# BACKPMAN21_CPU.net
KiCad netlist of a schematic drawn in Altium Designer
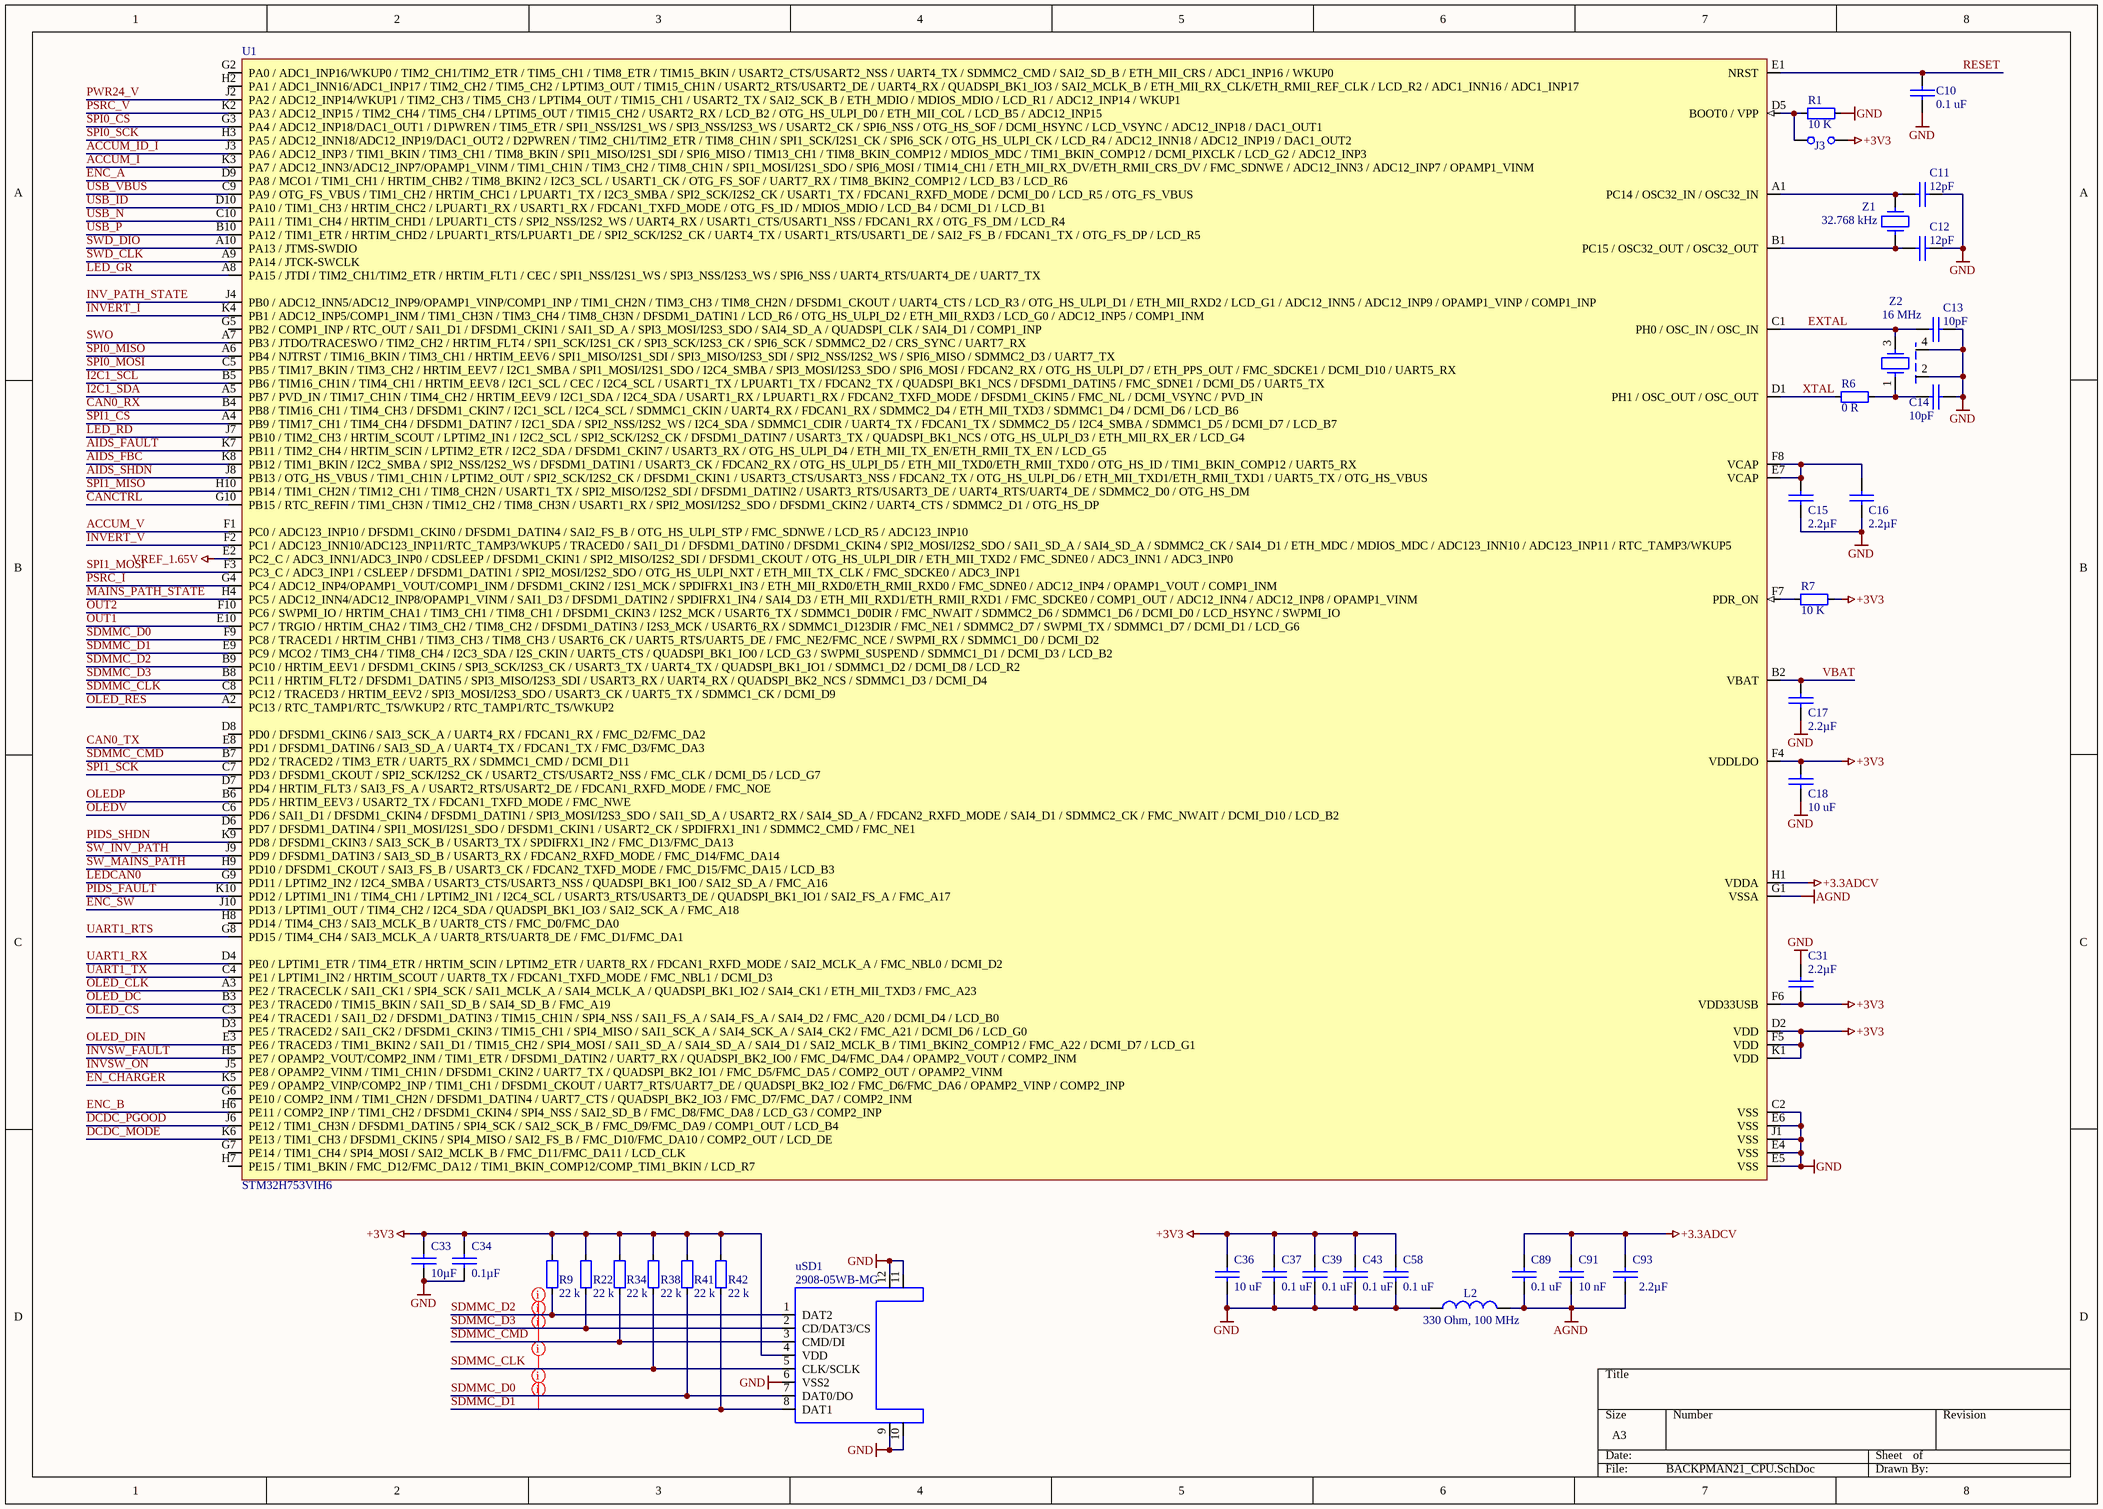
[diagram p0: BACKPMAN21_CPU.SchDoc]

(export (version "E")
  (design (tool "Eeschema 10.0.6"))
  (components
    (comp (ref "C10")
      (value "0.1 uF")
      (footprint "1608[0603]")
      (description "0.1 uF, 50V, 10% , X7R,  0603 SMD MLC Capacitor")
      (fields (field (name "TOLERANCE") "±10%") (field (name "MANUFACTURER") "WALSIN"))
      (libsource (lib "ea_Capacitors") (part "CVNF100K0603-25"))
    )
    (comp (ref "C11")
      (value "12pF")
      (footprint "0402 CAP")
      (description "12pF, ±2%, 50V, C0G, NP0, 0402 (1005 Metric), -55°C ~ 125°C, -, General Purpose")
      (fields
        (field (name "PART NUMBER") "0402N120G500CT")
        (field (name "MANUFACTURER") "Walsin Technology Corporation")
      )
      (libsource (lib "ea_PassivComps") (part "Capacitor"))
    )
    (comp (ref "C12")
      (value "12pF")
      (footprint "0402 CAP")
      (description "12pF, ±2%, 50V, C0G, NP0, 0402 (1005 Metric), -55°C ~ 125°C, -, General Purpose")
      (fields
        (field (name "PART NUMBER") "0402N120G500CT")
        (field (name "MANUFACTURER") "Walsin Technology Corporation")
      )
      (libsource (lib "ea_PassivComps") (part "Capacitor"))
    )
    (comp (ref "C13")
      (value "10pF")
      (footprint "0402 CAP")
      (description "10pF, ±1%, 50V, C0G, NP0, 0402 (1005 Metric), -55°C ~ 125°C, -, Automotive")
      (fields
        (field (name "PART NUMBER") "GCM1555C1H100FA16D")
        (field (name "MANUFACTURER") "Murata Electronics North America")
      )
      (libsource (lib "ea_PassivComps") (part "Capacitor"))
    )
    (comp (ref "C14")
      (value "10pF")
      (footprint "0402 CAP")
      (description "10pF, ±1%, 50V, C0G, NP0, 0402 (1005 Metric), -55°C ~ 125°C, -, Automotive")
      (fields
        (field (name "PART NUMBER") "GCM1555C1H100FA16D")
        (field (name "MANUFACTURER") "Murata Electronics North America")
      )
      (libsource (lib "ea_PassivComps") (part "Capacitor"))
    )
    (comp (ref "C15")
      (value "2.2µF")
      (footprint "0603 CAP")
      (description "2.2µF, ±10%, 16V, X5R, 0603 (1608 Metric), -55°C ~ 85°C, -, General Purpose")
      (fields (field (name "PART NUMBER") "CC0603KRX5R7BB225") (field (name "MANUFACTURER") "Yageo"))
      (libsource (lib "ea_PassivComps") (part "Capacitor"))
    )
    (comp (ref "C16")
      (value "2.2µF")
      (footprint "0603 CAP")
      (description "2.2µF, ±10%, 16V, X5R, 0603 (1608 Metric), -55°C ~ 85°C, -, General Purpose")
      (fields (field (name "PART NUMBER") "CC0603KRX5R7BB225") (field (name "MANUFACTURER") "Yageo"))
      (libsource (lib "ea_PassivComps") (part "Capacitor"))
    )
    (comp (ref "C17")
      (value "2.2µF")
      (footprint "0603 CAP")
      (description "2.2µF, ±10%, 16V, X5R, 0603 (1608 Metric), -55°C ~ 85°C, -, General Purpose")
      (fields (field (name "PART NUMBER") "CC0603KRX5R7BB225") (field (name "MANUFACTURER") "Yageo"))
      (libsource (lib "ea_PassivComps") (part "Capacitor"))
    )
    (comp (ref "C18")
      (value "10 uF")
      (footprint "0805-1206")
      (description "CAP CER 10UF 10V 10% X5R 0805")
      (fields (field (name "MANUFACTURER") "Taiyo Yuden") (field (name "TOLERANCE") "10%"))
      (libsource (lib "ea_Capacitors") (part "LMK212F106ZG-T"))
    )
    (comp (ref "C31")
      (value "2.2µF")
      (footprint "0603 CAP")
      (description "2.2µF, ±10%, 16V, X5R, 0603 (1608 Metric), -55°C ~ 85°C, -, General Purpose")
      (fields (field (name "PART NUMBER") "CC0603KRX5R7BB225") (field (name "MANUFACTURER") "Yageo"))
      (libsource (lib "ea_PassivComps") (part "Capacitor"))
    )
    (comp (ref "C33")
      (value "10µF")
      (footprint "0603 CAP")
      (description "10µF, ±10%, 16V, X5R, 0603 (1608 Metric), -55°C ~ 85°C, -, Automotive")
      (fields
        (field (name "PART NUMBER") "GRT188R61C106KE13D")
        (field (name "MANUFACTURER") "Murata Electronics North America")
      )
      (libsource (lib "ea_PassivComps") (part "Capacitor"))
    )
    (comp (ref "C34")
      (value "0.1µF")
      (footprint "0402 CAP")
      (description "0.1µF, ±10%, 50V, X7R, 0402 (1005 Metric), -55°C ~ 125°C, -, General Purpose")
      (fields
        (field (name "PART NUMBER") "0402B104K500CT")
        (field (name "MANUFACTURER") "Walsin Technology Corporation")
      )
      (libsource (lib "ea_PassivComps") (part "Capacitor"))
    )
    (comp (ref "C36")
      (value "10 uF")
      (footprint "0805-1206")
      (description "CAP CER 10UF 10V 10% X5R 0805")
      (fields (field (name "MANUFACTURER") "Taiyo Yuden") (field (name "TOLERANCE") "10%"))
      (libsource (lib "ea_Capacitors") (part "LMK212F106ZG-T"))
    )
    (comp (ref "C37")
      (value "0.1 uF")
      (footprint "1608[0603]")
      (description "0.1 uF, 50V, 10% , X7R,  0603 SMD MLC Capacitor")
      (fields (field (name "TOLERANCE") "±10%") (field (name "MANUFACTURER") "WALSIN"))
      (libsource (lib "ea_Capacitors") (part "CVNF100K0603-25"))
    )
    (comp (ref "C39")
      (value "0.1 uF")
      (footprint "1608[0603]")
      (description "0.1 uF, 50V, 10% , X7R,  0603 SMD MLC Capacitor")
      (fields (field (name "TOLERANCE") "±10%") (field (name "MANUFACTURER") "WALSIN"))
      (libsource (lib "ea_Capacitors") (part "CVNF100K0603-25"))
    )
    (comp (ref "C43")
      (value "0.1 uF")
      (footprint "1608[0603]")
      (description "0.1 uF, 50V, 10% , X7R,  0603 SMD MLC Capacitor")
      (fields (field (name "TOLERANCE") "±10%") (field (name "MANUFACTURER") "WALSIN"))
      (libsource (lib "ea_Capacitors") (part "CVNF100K0603-25"))
    )
    (comp (ref "C58")
      (value "0.1 uF")
      (footprint "1608[0603]")
      (description "0.1 uF, 50V, 10% , X7R,  0603 SMD MLC Capacitor")
      (fields (field (name "TOLERANCE") "±10%") (field (name "MANUFACTURER") "WALSIN"))
      (libsource (lib "ea_Capacitors") (part "CVNF100K0603-25"))
    )
    (comp (ref "C89")
      (value "0.1 uF")
      (footprint "1608[0603]")
      (description "0.1 uF, 50V, 10% , X7R,  0603 SMD MLC Capacitor")
      (fields (field (name "TOLERANCE") "±10%") (field (name "MANUFACTURER") "WALSIN"))
      (libsource (lib "ea_Capacitors") (part "CVNF100K0603-25"))
    )
    (comp (ref "C91")
      (value "10 nF")
      (footprint "1608[0603]")
      (description "10 nF, 50V, 10%, X7R, 0603 SMD MLC Capacitor")
      (fields (field (name "TOLERANCE") "±10%") (field (name "MANUFACTURER") "Murata Electronics"))
      (libsource (lib "ea_Capacitors") (part "CVNF010K0603"))
    )
    (comp (ref "C93")
      (value "2.2µF")
      (footprint "0603 CAP")
      (description "2.2µF, ±10%, 16V, X5R, 0603 (1608 Metric), -55°C ~ 85°C, -, General Purpose")
      (fields (field (name "PART NUMBER") "CC0603KRX5R7BB225") (field (name "MANUFACTURER") "Yageo"))
      (libsource (lib "ea_PassivComps") (part "Capacitor"))
    )
    (comp (ref "J3")
      (value "PH1-02-TA-HT")
      (footprint "HDR1X2V")
      (description "2 Pos. 2.54 mm Single Row Through Hole Straight Pin Header")
      (fields (field (name "MANUFACTURER") "ADAM TECH"))
      (libsource (lib "ea_Commutation") (part "Jumper"))
    )
    (comp (ref "L2")
      (value "330 Ohm, 100 MHz")
      (footprint "0603")
      (description "Ferrite bead, 330 Ohm, 100 MHz,  1.5 A, 0.07 Ohm")
      (fields
        (field (name "MANUFACTURER") "Murata Electronics North America")
        (field (name "PARTNUM") "BLM18SG331TN1D")
      )
      (libsource (lib "*") (part "BLM18SG331TN1D"))
    )
    (comp (ref "R1")
      (value "10 K")
      (footprint "0603")
      (description "10 K, 1%, 0603, SMD Resistor, Taped")
      (fields (field (name "MANUFACTURER") "Vishay") (field (name "TOLERANCE") "1%"))
      (libsource (lib "ea_Resistors_0603") (part "RL0603K010-1"))
    )
    (comp (ref "R6")
      (value "0 R")
      (footprint "0603")
      (description "0 R, Jumper, 0603, SMD Resistor, -55°C ~ 155°C")
      (fields (field (name "MANUFACTURER") "Yageo") (field (name "VOLTAGE") "75 V"))
      (libsource (lib "ea_Resistors_0603") (part "RC0603FR-070RL"))
    )
    (comp (ref "R7")
      (value "10 K")
      (footprint "0603")
      (description "10 K, 1%, 0603, SMD Resistor, Taped")
      (fields (field (name "MANUFACTURER") "Vishay") (field (name "TOLERANCE") "1%"))
      (libsource (lib "ea_Resistors_0603") (part "RL0603K010-1"))
    )
    (comp (ref "R9")
      (value "22 k")
      (footprint "0402")
      (fields
        (field (name "MANUFACTURER") "Stackpole Electronics Inc")
        (field (name "TOLERANCE") "±1%")
        (field (name "VOLTAGE") "75V")
      )
      (libsource (lib "ea_PassivComps") (part "Resistor"))
    )
    (comp (ref "R22")
      (value "22 k")
      (footprint "0402")
      (fields
        (field (name "MANUFACTURER") "Stackpole Electronics Inc")
        (field (name "TOLERANCE") "±1%")
        (field (name "VOLTAGE") "75V")
      )
      (libsource (lib "ea_PassivComps") (part "Resistor"))
    )
    (comp (ref "R34")
      (value "22 k")
      (footprint "0402")
      (fields
        (field (name "MANUFACTURER") "Stackpole Electronics Inc")
        (field (name "TOLERANCE") "±1%")
        (field (name "VOLTAGE") "75V")
      )
      (libsource (lib "ea_PassivComps") (part "Resistor"))
    )
    (comp (ref "R38")
      (value "22 k")
      (footprint "0402")
      (fields
        (field (name "MANUFACTURER") "Stackpole Electronics Inc")
        (field (name "TOLERANCE") "±1%")
        (field (name "VOLTAGE") "75V")
      )
      (libsource (lib "ea_PassivComps") (part "Resistor"))
    )
    (comp (ref "R41")
      (value "22 k")
      (footprint "0402")
      (fields
        (field (name "MANUFACTURER") "Stackpole Electronics Inc")
        (field (name "TOLERANCE") "±1%")
        (field (name "VOLTAGE") "75V")
      )
      (libsource (lib "ea_PassivComps") (part "Resistor"))
    )
    (comp (ref "R42")
      (value "22 k")
      (footprint "0402")
      (fields
        (field (name "MANUFACTURER") "Stackpole Electronics Inc")
        (field (name "TOLERANCE") "±1%")
        (field (name "VOLTAGE") "75V")
      )
      (libsource (lib "ea_PassivComps") (part "Resistor"))
    )
    (comp (ref "U1")
      (value "STM32H753VIH6")
      (footprint "TFBGA100")
      (description "Cortex-M7, 480MHz 2MB FLASH, 1MB RAM, 100-TFBGA (8x8)")
      (fields (field (name "MANUFACTURER") "STMicroelectronics") (field (name "PARTNUM") "STM32H753VIH6-ND"))
      (libsource (lib "ea_IC_CPU") (part "STM32H753VIH6"))
    )
    (comp (ref "uSD1")
      (value "2908-05WB-MG")
      (footprint "2908-05WB-MG")
      (description "microSD cadr holder")
      (fields (field (name "MANUFACTURER") "3M"))
      (libsource (lib "ea_CARD_holders") (part "2908-05WB-MG"))
    )
    (comp (ref "Z1")
      (value "32.768 kHz")
      (footprint "ABS7")
      (description "32.768 kHz, 12.5 pF, 70 kOhm, ±20ppm, 3.2 x 1.5 mm, -40°C ~ 85°C")
      (fields (field (name "MANUFACTURER") "Abracon Corporation") (field (name "PARTNUM") "535-9542-1-ND"))
      (libsource (lib "ea_OSC_CLK_GEN") (part "ABS07-32.768KHZ-T"))
    )
    (comp (ref "Z2")
      (value "16 MHz")
      (footprint "4-SMD 2.00mm x 1.60mm")
      (description "16 MHz, 9 pF, ±10ppm, 2.00mm x 1.60mm, -20°C ~ 70°C")
      (fields (field (name "MANUFACTURER") "Abracon LLC") (field (name "PARTNUM") "535-13598-1-ND"))
      (libsource (lib "ea_OSC_CLK_GEN") (part "ABM11-16.000MHZ-9-B1U-T"))
    )
  )
  (nets
    (net (code "1") (name "+3.3ADCV") (class "Default")
      (node (ref "C89") (pin "2") (pinfunction "2_2") (pintype "passive"))
      (node (ref "C91") (pin "1") (pinfunction "1_1") (pintype "passive"))
      (node (ref "C93") (pin "1") (pinfunction "1_1") (pintype "passive"))
      (node (ref "U1") (pin "H1") (pinfunction "VDDA_H1") (pintype "power_in"))
    )
    (net (code "2") (name "+3V3") (class "Default")
      (node (ref "C18") (pin "2") (pinfunction "2_2") (pintype "passive"))
      (node (ref "C31") (pin "2") (pinfunction "2_2") (pintype "passive"))
      (node (ref "C33") (pin "2") (pinfunction "2_2") (pintype "passive"))
      (node (ref "C34") (pin "2") (pinfunction "2_2") (pintype "passive"))
      (node (ref "C36") (pin "2") (pinfunction "2_2") (pintype "passive"))
      (node (ref "C37") (pin "2") (pinfunction "2_2") (pintype "passive"))
      (node (ref "C39") (pin "2") (pinfunction "2_2") (pintype "passive"))
      (node (ref "C43") (pin "2") (pinfunction "2_2") (pintype "passive"))
      (node (ref "C58") (pin "2") (pinfunction "2_2") (pintype "passive"))
      (node (ref "J3") (pin "2") (pinfunction "2_2") (pintype "passive"))
      (node (ref "R22") (pin "2") (pinfunction "2_2") (pintype "passive"))
      (node (ref "R34") (pin "2") (pinfunction "2_2") (pintype "passive"))
      (node (ref "R38") (pin "2") (pinfunction "2_2") (pintype "passive"))
      (node (ref "R41") (pin "2") (pinfunction "2_2") (pintype "passive"))
      (node (ref "R42") (pin "2") (pinfunction "2_2") (pintype "passive"))
      (node (ref "R7") (pin "1") (pinfunction "1_1") (pintype "passive"))
      (node (ref "R9") (pin "2") (pinfunction "2_2") (pintype "passive"))
      (node (ref "U1") (pin "D2") (pinfunction "VDD_D2") (pintype "power_in"))
      (node (ref "U1") (pin "F4") (pinfunction "VDDLDO_F4") (pintype "power_in"))
      (node (ref "U1") (pin "F5") (pinfunction "VDD_F5") (pintype "power_in"))
      (node (ref "U1") (pin "F6") (pinfunction "VDD33USB_F6") (pintype "power_in"))
      (node (ref "U1") (pin "K1") (pinfunction "VDD_K1") (pintype "power_in"))
      (node (ref "uSD1") (pin "4") (pinfunction "VDD_4") (pintype "passive"))
    )
    (net (code "3") (name "/ACCUM_I") (class "Default")
      (node (ref "U1") (pin "K3") (pinfunction "PA7_/_ADC12_INN3/ADC12_INP7/OPAMP1_VINM_/_TIM1_CH1N_/_TIM3_CH2_/_TIM8_CH1N_/_SPI1_MOSI/I2S1_SDO_/_SPI6_MOSI_/_TIM14_CH1_/_ETH_MII_RX_DV/ETH_RMII_CRS_DV_/_FMC_SDNWE_/_ADC12_INN3_/_ADC12_INP7_/_OPAMP1_VINM_K3") (pintype "bidirectional"))
    )
    (net (code "4") (name "/ACCUM_ID_I") (class "Default")
      (node (ref "U1") (pin "J3") (pinfunction "PA6_/_ADC12_INP3_/_TIM1_BKIN_/_TIM3_CH1_/_TIM8_BKIN_/_SPI1_MISO/I2S1_SDI_/_SPI6_MISO_/_TIM13_CH1_/_TIM8_BKIN_COMP12_/_MDIOS_MDC_/_TIM1_BKIN_COMP12_/_DCMI_PIXCLK_/_LCD_G2_/_ADC12_INP3_J3") (pintype "bidirectional"))
    )
    (net (code "5") (name "/ACCUM_V") (class "Default")
      (node (ref "U1") (pin "F1") (pinfunction "PC0_/_ADC123_INP10_/_DFSDM1_CKIN0_/_DFSDM1_DATIN4_/_SAI2_FS_B_/_OTG_HS_ULPI_STP_/_FMC_SDNWE_/_LCD_R5_/_ADC123_INP10_F1") (pintype "bidirectional"))
    )
    (net (code "6") (name "/AIDS_FAULT") (class "Default")
      (node (ref "U1") (pin "K7") (pinfunction "PB11_/_TIM2_CH4_/_HRTIM_SCIN_/_LPTIM2_ETR_/_I2C2_SDA_/_DFSDM1_CKIN7_/_USART3_RX_/_OTG_HS_ULPI_D4_/_ETH_MII_TX_EN/ETH_RMII_TX_EN_/_LCD_G5_K7") (pintype "bidirectional"))
    )
    (net (code "7") (name "/AIDS_FBC") (class "Default")
      (node (ref "U1") (pin "K8") (pinfunction "PB12_/_TIM1_BKIN_/_I2C2_SMBA_/_SPI2_NSS/I2S2_WS_/_DFSDM1_DATIN1_/_USART3_CK_/_FDCAN2_RX_/_OTG_HS_ULPI_D5_/_ETH_MII_TXD0/ETH_RMII_TXD0_/_OTG_HS_ID_/_TIM1_BKIN_COMP12_/_UART5_RX_K8") (pintype "bidirectional"))
    )
    (net (code "8") (name "/AIDS_SHDN") (class "Default")
      (node (ref "U1") (pin "J8") (pinfunction "PB13_/_OTG_HS_VBUS_/_TIM1_CH1N_/_LPTIM2_OUT_/_SPI2_SCK/I2S2_CK_/_DFSDM1_CKIN1_/_USART3_CTS/USART3_NSS_/_FDCAN2_TX_/_OTG_HS_ULPI_D6_/_ETH_MII_TXD1/ETH_RMII_TXD1_/_UART5_TX_/_OTG_HS_VBUS_J8") (pintype "bidirectional"))
    )
    (net (code "9") (name "/CAN0_RX") (class "Default")
      (node (ref "U1") (pin "B4") (pinfunction "PB8_/_TIM16_CH1_/_TIM4_CH3_/_DFSDM1_CKIN7_/_I2C1_SCL_/_I2C4_SCL_/_SDMMC1_CKIN_/_UART4_RX_/_FDCAN1_RX_/_SDMMC2_D4_/_ETH_MII_TXD3_/_SDMMC1_D4_/_DCMI_D6_/_LCD_B6_B4") (pintype "bidirectional"))
    )
    (net (code "10") (name "/CAN0_TX") (class "Default")
      (node (ref "U1") (pin "E8") (pinfunction "PD1_/_DFSDM1_DATIN6_/_SAI3_SD_A_/_UART4_TX_/_FDCAN1_TX_/_FMC_D3/FMC_DA3_E8") (pintype "bidirectional"))
    )
    (net (code "11") (name "/CANCTRL") (class "Default")
      (node (ref "U1") (pin "G10") (pinfunction "PB15_/_RTC_REFIN_/_TIM1_CH3N_/_TIM12_CH2_/_TIM8_CH3N_/_USART1_RX_/_SPI2_MOSI/I2S2_SDO_/_DFSDM1_CKIN2_/_UART4_CTS_/_SDMMC2_D1_/_OTG_HS_DP_G10") (pintype "bidirectional"))
    )
    (net (code "12") (name "/DCDC_MODE") (class "Default")
      (node (ref "U1") (pin "K6") (pinfunction "PE13_/_TIM1_CH3_/_DFSDM1_CKIN5_/_SPI4_MISO_/_SAI2_FS_B_/_FMC_D10/FMC_DA10_/_COMP2_OUT_/_LCD_DE_K6") (pintype "bidirectional"))
    )
    (net (code "13") (name "/DCDC_PGOOD") (class "Default")
      (node (ref "U1") (pin "J6") (pinfunction "PE12_/_TIM1_CH3N_/_DFSDM1_DATIN5_/_SPI4_SCK_/_SAI2_SCK_B_/_FMC_D9/FMC_DA9_/_COMP1_OUT_/_LCD_B4_J6") (pintype "bidirectional"))
    )
    (net (code "14") (name "/ENC_A") (class "Default")
      (node (ref "U1") (pin "D9") (pinfunction "PA8_/_MCO1_/_TIM1_CH1_/_HRTIM_CHB2_/_TIM8_BKIN2_/_I2C3_SCL_/_USART1_CK_/_OTG_FS_SOF_/_UART7_RX_/_TIM8_BKIN2_COMP12_/_LCD_B3_/_LCD_R6_D9") (pintype "bidirectional"))
    )
    (net (code "15") (name "/ENC_B") (class "Default")
      (node (ref "U1") (pin "H6") (pinfunction "PE11_/_COMP2_INP_/_TIM1_CH2_/_DFSDM1_CKIN4_/_SPI4_NSS_/_SAI2_SD_B_/_FMC_D8/FMC_DA8_/_LCD_G3_/_COMP2_INP_H6") (pintype "bidirectional"))
    )
    (net (code "16") (name "/ENC_SW") (class "Default")
      (node (ref "U1") (pin "J10") (pinfunction "PD13_/_LPTIM1_OUT_/_TIM4_CH2_/_I2C4_SDA_/_QUADSPI_BK1_IO3_/_SAI2_SCK_A_/_FMC_A18_J10") (pintype "bidirectional"))
    )
    (net (code "17") (name "/EN_CHARGER") (class "Default")
      (node (ref "U1") (pin "K5") (pinfunction "PE9_/_OPAMP2_VINP/COMP2_INP_/_TIM1_CH1_/_DFSDM1_CKOUT_/_UART7_RTS/UART7_DE_/_QUADSPI_BK2_IO2_/_FMC_D6/FMC_DA6_/_OPAMP2_VINP_/_COMP2_INP_K5") (pintype "bidirectional"))
    )
    (net (code "18") (name "/EXTAL") (class "Default")
      (node (ref "C13") (pin "1") (pinfunction "1_1") (pintype "passive"))
      (node (ref "U1") (pin "C1") (pinfunction "PH0_/_OSC_IN_/_OSC_IN_C1") (pintype "bidirectional"))
      (node (ref "Z2") (pin "3") (pinfunction "3_3") (pintype "passive"))
    )
    (net (code "19") (name "/I2C1_SCL") (class "Default")
      (node (ref "U1") (pin "B5") (pinfunction "PB6_/_TIM16_CH1N_/_TIM4_CH1_/_HRTIM_EEV8_/_I2C1_SCL_/_CEC_/_I2C4_SCL_/_USART1_TX_/_LPUART1_TX_/_FDCAN2_TX_/_QUADSPI_BK1_NCS_/_DFSDM1_DATIN5_/_FMC_SDNE1_/_DCMI_D5_/_UART5_TX_B5") (pintype "bidirectional"))
    )
    (net (code "20") (name "/I2C1_SDA") (class "Default")
      (node (ref "U1") (pin "A5") (pinfunction "PB7_/_PVD_IN_/_TIM17_CH1N_/_TIM4_CH2_/_HRTIM_EEV9_/_I2C1_SDA_/_I2C4_SDA_/_USART1_RX_/_LPUART1_RX_/_FDCAN2_TXFD_MODE_/_DFSDM1_CKIN5_/_FMC_NL_/_DCMI_VSYNC_/_PVD_IN_A5") (pintype "bidirectional"))
    )
    (net (code "21") (name "/INVERT_I") (class "Default")
      (node (ref "U1") (pin "K4") (pinfunction "PB1_/_ADC12_INP5/COMP1_INM_/_TIM1_CH3N_/_TIM3_CH4_/_TIM8_CH3N_/_DFSDM1_DATIN1_/_LCD_R6_/_OTG_HS_ULPI_D2_/_ETH_MII_RXD3_/_LCD_G0_/_ADC12_INP5_/_COMP1_INM_K4") (pintype "bidirectional"))
    )
    (net (code "22") (name "/INVERT_V") (class "Default")
      (node (ref "U1") (pin "F2") (pinfunction "PC1_/_ADC123_INN10/ADC123_INP11/RTC_TAMP3/WKUP5_/_TRACED0_/_SAI1_D1_/_DFSDM1_DATIN0_/_DFSDM1_CKIN4_/_SPI2_MOSI/I2S2_SDO_/_SAI1_SD_A_/_SAI4_SD_A_/_SDMMC2_CK_/_SAI4_D1_/_ETH_MDC_/_MDIOS_MDC_/_ADC123_INN10_/_ADC123_INP11_/_RTC_TAMP3/WKUP5_F2") (pintype "bidirectional"))
    )
    (net (code "23") (name "/INVSW_FAULT") (class "Default")
      (node (ref "U1") (pin "H5") (pinfunction "PE7_/_OPAMP2_VOUT/COMP2_INM_/_TIM1_ETR_/_DFSDM1_DATIN2_/_UART7_RX_/_QUADSPI_BK2_IO0_/_FMC_D4/FMC_DA4_/_OPAMP2_VOUT_/_COMP2_INM_H5") (pintype "bidirectional"))
    )
    (net (code "24") (name "/INVSW_ON") (class "Default")
      (node (ref "U1") (pin "J5") (pinfunction "PE8_/_OPAMP2_VINM_/_TIM1_CH1N_/_DFSDM1_CKIN2_/_UART7_TX_/_QUADSPI_BK2_IO1_/_FMC_D5/FMC_DA5_/_COMP2_OUT_/_OPAMP2_VINM_J5") (pintype "bidirectional"))
    )
    (net (code "25") (name "/INV_PATH_STATE") (class "Default")
      (node (ref "U1") (pin "J4") (pinfunction "PB0_/_ADC12_INN5/ADC12_INP9/OPAMP1_VINP/COMP1_INP_/_TIM1_CH2N_/_TIM3_CH3_/_TIM8_CH2N_/_DFSDM1_CKOUT_/_UART4_CTS_/_LCD_R3_/_OTG_HS_ULPI_D1_/_ETH_MII_RXD2_/_LCD_G1_/_ADC12_INN5_/_ADC12_INP9_/_OPAMP1_VINP_/_COMP1_INP_J4") (pintype "bidirectional"))
    )
    (net (code "26") (name "/LEDCAN0") (class "Default")
      (node (ref "U1") (pin "G9") (pinfunction "PD11_/_LPTIM2_IN2_/_I2C4_SMBA_/_USART3_CTS/USART3_NSS_/_QUADSPI_BK1_IO0_/_SAI2_SD_A_/_FMC_A16_G9") (pintype "bidirectional"))
    )
    (net (code "27") (name "/LED_GR") (class "Default")
      (node (ref "U1") (pin "A8") (pinfunction "PA15_/_JTDI_/_TIM2_CH1/TIM2_ETR_/_HRTIM_FLT1_/_CEC_/_SPI1_NSS/I2S1_WS_/_SPI3_NSS/I2S3_WS_/_SPI6_NSS_/_UART4_RTS/UART4_DE_/_UART7_TX_A8") (pintype "bidirectional"))
    )
    (net (code "28") (name "/LED_RD") (class "Default")
      (node (ref "U1") (pin "J7") (pinfunction "PB10_/_TIM2_CH3_/_HRTIM_SCOUT_/_LPTIM2_IN1_/_I2C2_SCL_/_SPI2_SCK/I2S2_CK_/_DFSDM1_DATIN7_/_USART3_TX_/_QUADSPI_BK1_NCS_/_OTG_HS_ULPI_D3_/_ETH_MII_RX_ER_/_LCD_G4_J7") (pintype "bidirectional"))
    )
    (net (code "29") (name "/MAINS_PATH_STATE") (class "Default")
      (node (ref "U1") (pin "H4") (pinfunction "PC5_/_ADC12_INN4/ADC12_INP8/OPAMP1_VINM_/_SAI1_D3_/_DFSDM1_DATIN2_/_SPDIFRX1_IN4_/_SAI4_D3_/_ETH_MII_RXD1/ETH_RMII_RXD1_/_FMC_SDCKE0_/_COMP1_OUT_/_ADC12_INN4_/_ADC12_INP8_/_OPAMP1_VINM_H4") (pintype "bidirectional"))
    )
    (net (code "30") (name "/OLEDP") (class "Default")
      (node (ref "U1") (pin "B6") (pinfunction "PD5_/_HRTIM_EEV3_/_USART2_TX_/_FDCAN1_TXFD_MODE_/_FMC_NWE_B6") (pintype "bidirectional"))
    )
    (net (code "31") (name "/OLEDV") (class "Default")
      (node (ref "U1") (pin "C6") (pinfunction "PD6_/_SAI1_D1_/_DFSDM1_CKIN4_/_DFSDM1_DATIN1_/_SPI3_MOSI/I2S3_SDO_/_SAI1_SD_A_/_USART2_RX_/_SAI4_SD_A_/_FDCAN2_RXFD_MODE_/_SAI4_D1_/_SDMMC2_CK_/_FMC_NWAIT_/_DCMI_D10_/_LCD_B2_C6") (pintype "bidirectional"))
    )
    (net (code "32") (name "/OLED_CLK") (class "Default")
      (node (ref "U1") (pin "A3") (pinfunction "PE2_/_TRACECLK_/_SAI1_CK1_/_SPI4_SCK_/_SAI1_MCLK_A_/_SAI4_MCLK_A_/_QUADSPI_BK1_IO2_/_SAI4_CK1_/_ETH_MII_TXD3_/_FMC_A23_A3") (pintype "bidirectional"))
    )
    (net (code "33") (name "/OLED_CS") (class "Default")
      (node (ref "U1") (pin "C3") (pinfunction "PE4_/_TRACED1_/_SAI1_D2_/_DFSDM1_DATIN3_/_TIM15_CH1N_/_SPI4_NSS_/_SAI1_FS_A_/_SAI4_FS_A_/_SAI4_D2_/_FMC_A20_/_DCMI_D4_/_LCD_B0_C3") (pintype "bidirectional"))
    )
    (net (code "34") (name "/OLED_DC") (class "Default")
      (node (ref "U1") (pin "B3") (pinfunction "PE3_/_TRACED0_/_TIM15_BKIN_/_SAI1_SD_B_/_SAI4_SD_B_/_FMC_A19_B3") (pintype "bidirectional"))
    )
    (net (code "35") (name "/OLED_DIN") (class "Default")
      (node (ref "U1") (pin "E3") (pinfunction "PE6_/_TRACED3_/_TIM1_BKIN2_/_SAI1_D1_/_TIM15_CH2_/_SPI4_MOSI_/_SAI1_SD_A_/_SAI4_SD_A_/_SAI4_D1_/_SAI2_MCLK_B_/_TIM1_BKIN2_COMP12_/_FMC_A22_/_DCMI_D7_/_LCD_G1_E3") (pintype "bidirectional"))
    )
    (net (code "36") (name "/OLED_RES") (class "Default")
      (node (ref "U1") (pin "A2") (pinfunction "PC13_/_RTC_TAMP1/RTC_TS/WKUP2_/_RTC_TAMP1/RTC_TS/WKUP2_A2") (pintype "bidirectional"))
    )
    (net (code "37") (name "/OUT1") (class "Default")
      (node (ref "U1") (pin "E10") (pinfunction "PC7_/_TRGIO_/_HRTIM_CHA2_/_TIM3_CH2_/_TIM8_CH2_/_DFSDM1_DATIN3_/_I2S3_MCK_/_USART6_RX_/_SDMMC1_D123DIR_/_FMC_NE1_/_SDMMC2_D7_/_SWPMI_TX_/_SDMMC1_D7_/_DCMI_D1_/_LCD_G6_E10") (pintype "bidirectional"))
    )
    (net (code "38") (name "/OUT2") (class "Default")
      (node (ref "U1") (pin "F10") (pinfunction "PC6_/_SWPMI_IO_/_HRTIM_CHA1_/_TIM3_CH1_/_TIM8_CH1_/_DFSDM1_CKIN3_/_I2S2_MCK_/_USART6_TX_/_SDMMC1_D0DIR_/_FMC_NWAIT_/_SDMMC2_D6_/_SDMMC1_D6_/_DCMI_D0_/_LCD_HSYNC_/_SWPMI_IO_F10") (pintype "bidirectional"))
    )
    (net (code "39") (name "/PIDS_FAULT") (class "Default")
      (node (ref "U1") (pin "K10") (pinfunction "PD12_/_LPTIM1_IN1_/_TIM4_CH1_/_LPTIM2_IN1_/_I2C4_SCL_/_USART3_RTS/USART3_DE_/_QUADSPI_BK1_IO1_/_SAI2_FS_A_/_FMC_A17_K10") (pintype "bidirectional"))
    )
    (net (code "40") (name "/PIDS_SHDN") (class "Default")
      (node (ref "U1") (pin "K9") (pinfunction "PD8_/_DFSDM1_CKIN3_/_SAI3_SCK_B_/_USART3_TX_/_SPDIFRX1_IN2_/_FMC_D13/FMC_DA13_K9") (pintype "bidirectional"))
    )
    (net (code "41") (name "/PSRC_I") (class "Default")
      (node (ref "U1") (pin "G4") (pinfunction "PC4_/_ADC12_INP4/OPAMP1_VOUT/COMP1_INM_/_DFSDM1_CKIN2_/_I2S1_MCK_/_SPDIFRX1_IN3_/_ETH_MII_RXD0/ETH_RMII_RXD0_/_FMC_SDNE0_/_ADC12_INP4_/_OPAMP1_VOUT_/_COMP1_INM_G4") (pintype "bidirectional"))
    )
    (net (code "42") (name "/PSRC_V") (class "Default")
      (node (ref "U1") (pin "K2") (pinfunction "PA3_/_ADC12_INP15_/_TIM2_CH4_/_TIM5_CH4_/_LPTIM5_OUT_/_TIM15_CH2_/_USART2_RX_/_LCD_B2_/_OTG_HS_ULPI_D0_/_ETH_MII_COL_/_LCD_B5_/_ADC12_INP15_K2") (pintype "bidirectional"))
    )
    (net (code "43") (name "/PWR24_V") (class "Default")
      (node (ref "U1") (pin "J2") (pinfunction "PA2_/_ADC12_INP14/WKUP1_/_TIM2_CH3_/_TIM5_CH3_/_LPTIM4_OUT_/_TIM15_CH1_/_USART2_TX_/_SAI2_SCK_B_/_ETH_MDIO_/_MDIOS_MDIO_/_LCD_R1_/_ADC12_INP14_/_WKUP1_J2") (pintype "bidirectional"))
    )
    (net (code "44") (name "/RESET") (class "Default")
      (node (ref "C10") (pin "1") (pinfunction "1_1") (pintype "passive"))
      (node (ref "U1") (pin "E1") (pinfunction "NRST_E1") (pintype "bidirectional"))
    )
    (net (code "45") (name "/SDMMC_CLK") (class "Default")
      (node (ref "R38") (pin "1") (pinfunction "1_1") (pintype "passive"))
      (node (ref "U1") (pin "C8") (pinfunction "PC12_/_TRACED3_/_HRTIM_EEV2_/_SPI3_MOSI/I2S3_SDO_/_USART3_CK_/_UART5_TX_/_SDMMC1_CK_/_DCMI_D9_C8") (pintype "bidirectional"))
      (node (ref "uSD1") (pin "5") (pinfunction "CLK/SCLK_5") (pintype "passive"))
    )
    (net (code "46") (name "/SDMMC_CMD") (class "Default")
      (node (ref "R34") (pin "1") (pinfunction "1_1") (pintype "passive"))
      (node (ref "U1") (pin "B7") (pinfunction "PD2_/_TRACED2_/_TIM3_ETR_/_UART5_RX_/_SDMMC1_CMD_/_DCMI_D11_B7") (pintype "bidirectional"))
      (node (ref "uSD1") (pin "3") (pinfunction "CMD/DI_3") (pintype "passive"))
    )
    (net (code "47") (name "/SDMMC_D0") (class "Default")
      (node (ref "R41") (pin "1") (pinfunction "1_1") (pintype "passive"))
      (node (ref "U1") (pin "F9") (pinfunction "PC8_/_TRACED1_/_HRTIM_CHB1_/_TIM3_CH3_/_TIM8_CH3_/_USART6_CK_/_UART5_RTS/UART5_DE_/_FMC_NE2/FMC_NCE_/_SWPMI_RX_/_SDMMC1_D0_/_DCMI_D2_F9") (pintype "bidirectional"))
      (node (ref "uSD1") (pin "7") (pinfunction "DAT0/DO_7") (pintype "passive"))
    )
    (net (code "48") (name "/SDMMC_D1") (class "Default")
      (node (ref "R42") (pin "1") (pinfunction "1_1") (pintype "passive"))
      (node (ref "U1") (pin "E9") (pinfunction "PC9_/_MCO2_/_TIM3_CH4_/_TIM8_CH4_/_I2C3_SDA_/_I2S_CKIN_/_UART5_CTS_/_QUADSPI_BK1_IO0_/_LCD_G3_/_SWPMI_SUSPEND_/_SDMMC1_D1_/_DCMI_D3_/_LCD_B2_E9") (pintype "bidirectional"))
      (node (ref "uSD1") (pin "8") (pinfunction "DAT1_8") (pintype "passive"))
    )
    (net (code "49") (name "/SDMMC_D2") (class "Default")
      (node (ref "R9") (pin "1") (pinfunction "1_1") (pintype "passive"))
      (node (ref "U1") (pin "B9") (pinfunction "PC10_/_HRTIM_EEV1_/_DFSDM1_CKIN5_/_SPI3_SCK/I2S3_CK_/_USART3_TX_/_UART4_TX_/_QUADSPI_BK1_IO1_/_SDMMC1_D2_/_DCMI_D8_/_LCD_R2_B9") (pintype "bidirectional"))
      (node (ref "uSD1") (pin "1") (pinfunction "DAT2_1") (pintype "passive"))
    )
    (net (code "50") (name "/SDMMC_D3") (class "Default")
      (node (ref "R22") (pin "1") (pinfunction "1_1") (pintype "passive"))
      (node (ref "U1") (pin "B8") (pinfunction "PC11_/_HRTIM_FLT2_/_DFSDM1_DATIN5_/_SPI3_MISO/I2S3_SDI_/_USART3_RX_/_UART4_RX_/_QUADSPI_BK2_NCS_/_SDMMC1_D3_/_DCMI_D4_B8") (pintype "bidirectional"))
      (node (ref "uSD1") (pin "2") (pinfunction "CD/DAT3/CS_2") (pintype "passive"))
    )
    (net (code "51") (name "/SPI0_CS") (class "Default")
      (node (ref "U1") (pin "G3") (pinfunction "PA4_/_ADC12_INP18/DAC1_OUT1_/_D1PWREN_/_TIM5_ETR_/_SPI1_NSS/I2S1_WS_/_SPI3_NSS/I2S3_WS_/_USART2_CK_/_SPI6_NSS_/_OTG_HS_SOF_/_DCMI_HSYNC_/_LCD_VSYNC_/_ADC12_INP18_/_DAC1_OUT1_G3") (pintype "bidirectional"))
    )
    (net (code "52") (name "/SPI0_MISO") (class "Default")
      (node (ref "U1") (pin "A6") (pinfunction "PB4_/_NJTRST_/_TIM16_BKIN_/_TIM3_CH1_/_HRTIM_EEV6_/_SPI1_MISO/I2S1_SDI_/_SPI3_MISO/I2S3_SDI_/_SPI2_NSS/I2S2_WS_/_SPI6_MISO_/_SDMMC2_D3_/_UART7_TX_A6") (pintype "bidirectional"))
    )
    (net (code "53") (name "/SPI0_MOSI") (class "Default")
      (node (ref "U1") (pin "C5") (pinfunction "PB5_/_TIM17_BKIN_/_TIM3_CH2_/_HRTIM_EEV7_/_I2C1_SMBA_/_SPI1_MOSI/I2S1_SDO_/_I2C4_SMBA_/_SPI3_MOSI/I2S3_SDO_/_SPI6_MOSI_/_FDCAN2_RX_/_OTG_HS_ULPI_D7_/_ETH_PPS_OUT_/_FMC_SDCKE1_/_DCMI_D10_/_UART5_RX_C5") (pintype "bidirectional"))
    )
    (net (code "54") (name "/SPI0_SCK") (class "Default")
      (node (ref "U1") (pin "H3") (pinfunction "PA5_/_ADC12_INN18/ADC12_INP19/DAC1_OUT2_/_D2PWREN_/_TIM2_CH1/TIM2_ETR_/_TIM8_CH1N_/_SPI1_SCK/I2S1_CK_/_SPI6_SCK_/_OTG_HS_ULPI_CK_/_LCD_R4_/_ADC12_INN18_/_ADC12_INP19_/_DAC1_OUT2_H3") (pintype "bidirectional"))
    )
    (net (code "55") (name "/SPI1_CS") (class "Default")
      (node (ref "U1") (pin "A4") (pinfunction "PB9_/_TIM17_CH1_/_TIM4_CH4_/_DFSDM1_DATIN7_/_I2C1_SDA_/_SPI2_NSS/I2S2_WS_/_I2C4_SDA_/_SDMMC1_CDIR_/_UART4_TX_/_FDCAN1_TX_/_SDMMC2_D5_/_I2C4_SMBA_/_SDMMC1_D5_/_DCMI_D7_/_LCD_B7_A4") (pintype "bidirectional"))
    )
    (net (code "56") (name "/SPI1_MISO") (class "Default")
      (node (ref "U1") (pin "H10") (pinfunction "PB14_/_TIM1_CH2N_/_TIM12_CH1_/_TIM8_CH2N_/_USART1_TX_/_SPI2_MISO/I2S2_SDI_/_DFSDM1_DATIN2_/_USART3_RTS/USART3_DE_/_UART4_RTS/UART4_DE_/_SDMMC2_D0_/_OTG_HS_DM_H10") (pintype "bidirectional"))
    )
    (net (code "57") (name "/SPI1_MOSI") (class "Default")
      (node (ref "U1") (pin "F3") (pinfunction "PC3_C_/_ADC3_INP1_/_CSLEEP_/_DFSDM1_DATIN1_/_SPI2_MOSI/I2S2_SDO_/_OTG_HS_ULPI_NXT_/_ETH_MII_TX_CLK_/_FMC_SDCKE0_/_ADC3_INP1_F3") (pintype "bidirectional"))
    )
    (net (code "58") (name "/SPI1_SCK") (class "Default")
      (node (ref "U1") (pin "C7") (pinfunction "PD3_/_DFSDM1_CKOUT_/_SPI2_SCK/I2S2_CK_/_USART2_CTS/USART2_NSS_/_FMC_CLK_/_DCMI_D5_/_LCD_G7_C7") (pintype "bidirectional"))
    )
    (net (code "59") (name "/SWD_CLK") (class "Default")
      (node (ref "U1") (pin "A9") (pinfunction "PA14_/_JTCK-SWCLK_A9") (pintype "bidirectional"))
    )
    (net (code "60") (name "/SWD_DIO") (class "Default")
      (node (ref "U1") (pin "A10") (pinfunction "PA13_/_JTMS-SWDIO_A10") (pintype "bidirectional"))
    )
    (net (code "61") (name "/SWO") (class "Default")
      (node (ref "U1") (pin "A7") (pinfunction "PB3_/_JTDO/TRACESWO_/_TIM2_CH2_/_HRTIM_FLT4_/_SPI1_SCK/I2S1_CK_/_SPI3_SCK/I2S3_CK_/_SPI6_SCK_/_SDMMC2_D2_/_CRS_SYNC_/_UART7_RX_A7") (pintype "bidirectional"))
    )
    (net (code "62") (name "/SW_INV_PATH") (class "Default")
      (node (ref "U1") (pin "J9") (pinfunction "PD9_/_DFSDM1_DATIN3_/_SAI3_SD_B_/_USART3_RX_/_FDCAN2_RXFD_MODE_/_FMC_D14/FMC_DA14_J9") (pintype "bidirectional"))
    )
    (net (code "63") (name "/SW_MAINS_PATH") (class "Default")
      (node (ref "U1") (pin "H9") (pinfunction "PD10_/_DFSDM1_CKOUT_/_SAI3_FS_B_/_USART3_CK_/_FDCAN2_TXFD_MODE_/_FMC_D15/FMC_DA15_/_LCD_B3_H9") (pintype "bidirectional"))
    )
    (net (code "64") (name "/UART1_RTS") (class "Default")
      (node (ref "U1") (pin "G8") (pinfunction "PD15_/_TIM4_CH4_/_SAI3_MCLK_A_/_UART8_RTS/UART8_DE_/_FMC_D1/FMC_DA1_G8") (pintype "bidirectional"))
    )
    (net (code "65") (name "/UART1_RX") (class "Default")
      (node (ref "U1") (pin "D4") (pinfunction "PE0_/_LPTIM1_ETR_/_TIM4_ETR_/_HRTIM_SCIN_/_LPTIM2_ETR_/_UART8_RX_/_FDCAN1_RXFD_MODE_/_SAI2_MCLK_A_/_FMC_NBL0_/_DCMI_D2_D4") (pintype "bidirectional"))
    )
    (net (code "66") (name "/UART1_TX") (class "Default")
      (node (ref "U1") (pin "C4") (pinfunction "PE1_/_LPTIM1_IN2_/_HRTIM_SCOUT_/_UART8_TX_/_FDCAN1_TXFD_MODE_/_FMC_NBL1_/_DCMI_D3_C4") (pintype "bidirectional"))
    )
    (net (code "67") (name "/USB_ID") (class "Default")
      (node (ref "U1") (pin "D10") (pinfunction "PA10_/_TIM1_CH3_/_HRTIM_CHC2_/_LPUART1_RX_/_USART1_RX_/_FDCAN1_TXFD_MODE_/_OTG_FS_ID_/_MDIOS_MDIO_/_LCD_B4_/_DCMI_D1_/_LCD_B1_D10") (pintype "bidirectional"))
    )
    (net (code "68") (name "/USB_N") (class "Default")
      (node (ref "U1") (pin "C10") (pinfunction "PA11_/_TIM1_CH4_/_HRTIM_CHD1_/_LPUART1_CTS_/_SPI2_NSS/I2S2_WS_/_UART4_RX_/_USART1_CTS/USART1_NSS_/_FDCAN1_RX_/_OTG_FS_DM_/_LCD_R4_C10") (pintype "bidirectional"))
    )
    (net (code "69") (name "/USB_P") (class "Default")
      (node (ref "U1") (pin "B10") (pinfunction "PA12_/_TIM1_ETR_/_HRTIM_CHD2_/_LPUART1_RTS/LPUART1_DE_/_SPI2_SCK/I2S2_CK_/_UART4_TX_/_USART1_RTS/USART1_DE_/_SAI2_FS_B_/_FDCAN1_TX_/_OTG_FS_DP_/_LCD_R5_B10") (pintype "bidirectional"))
    )
    (net (code "70") (name "/USB_VBUS") (class "Default")
      (node (ref "U1") (pin "C9") (pinfunction "PA9_/_OTG_FS_VBUS_/_TIM1_CH2_/_HRTIM_CHC1_/_LPUART1_TX_/_I2C3_SMBA_/_SPI2_SCK/I2S2_CK_/_USART1_TX_/_FDCAN1_RXFD_MODE_/_DCMI_D0_/_LCD_R5_/_OTG_FS_VBUS_C9") (pintype "bidirectional"))
    )
    (net (code "71") (name "/VBAT") (class "Default")
      (node (ref "C17") (pin "1") (pinfunction "1_1") (pintype "passive"))
      (node (ref "U1") (pin "B2") (pinfunction "VBAT_B2") (pintype "power_in"))
    )
    (net (code "72") (name "/XTAL") (class "Default")
      (node (ref "R6") (pin "2") (pinfunction "2_2") (pintype "passive"))
      (node (ref "U1") (pin "D1") (pinfunction "PH1_/_OSC_OUT_/_OSC_OUT_D1") (pintype "bidirectional"))
    )
    (net (code "73") (name "AGND") (class "Default")
      (node (ref "C89") (pin "1") (pinfunction "1_1") (pintype "passive"))
      (node (ref "C91") (pin "2") (pinfunction "2_2") (pintype "passive"))
      (node (ref "C93") (pin "2") (pinfunction "2_2") (pintype "passive"))
      (node (ref "L2") (pin "2") (pinfunction "2_2") (pintype "passive"))
      (node (ref "U1") (pin "G1") (pinfunction "VSSA_G1") (pintype "power_in"))
    )
    (net (code "74") (name "GND") (class "Default")
      (node (ref "C10") (pin "2") (pinfunction "2_2") (pintype "passive"))
      (node (ref "C11") (pin "2") (pinfunction "2_2") (pintype "passive"))
      (node (ref "C12") (pin "2") (pinfunction "2_2") (pintype "passive"))
      (node (ref "C13") (pin "2") (pinfunction "2_2") (pintype "passive"))
      (node (ref "C14") (pin "2") (pinfunction "2_2") (pintype "passive"))
      (node (ref "C15") (pin "2") (pinfunction "2_2") (pintype "passive"))
      (node (ref "C16") (pin "2") (pinfunction "2_2") (pintype "passive"))
      (node (ref "C17") (pin "2") (pinfunction "2_2") (pintype "passive"))
      (node (ref "C18") (pin "1") (pinfunction "1_1") (pintype "passive"))
      (node (ref "C31") (pin "1") (pinfunction "1_1") (pintype "passive"))
      (node (ref "C33") (pin "1") (pinfunction "1_1") (pintype "passive"))
      (node (ref "C34") (pin "1") (pinfunction "1_1") (pintype "passive"))
      (node (ref "C36") (pin "1") (pinfunction "1_1") (pintype "passive"))
      (node (ref "C37") (pin "1") (pinfunction "1_1") (pintype "passive"))
      (node (ref "C39") (pin "1") (pinfunction "1_1") (pintype "passive"))
      (node (ref "C43") (pin "1") (pinfunction "1_1") (pintype "passive"))
      (node (ref "C58") (pin "1") (pinfunction "1_1") (pintype "passive"))
      (node (ref "L2") (pin "1") (pinfunction "1_1") (pintype "passive"))
      (node (ref "R1") (pin "1") (pinfunction "1_1") (pintype "passive"))
      (node (ref "U1") (pin "C2") (pinfunction "VSS_C2") (pintype "power_in"))
      (node (ref "U1") (pin "E4") (pinfunction "VSS_E4") (pintype "power_in"))
      (node (ref "U1") (pin "E5") (pinfunction "VSS_E5") (pintype "power_in"))
      (node (ref "U1") (pin "E6") (pinfunction "VSS_E6") (pintype "power_in"))
      (node (ref "U1") (pin "J1") (pinfunction "VSS_J1") (pintype "power_in"))
      (node (ref "Z2") (pin "2") (pinfunction "2_2") (pintype "passive"))
      (node (ref "Z2") (pin "4") (pinfunction "4_4") (pintype "passive"))
      (node (ref "uSD1") (pin "10") (pinfunction "WP_10") (pintype "passive"))
      (node (ref "uSD1") (pin "11") (pinfunction "GND_11") (pintype "passive"))
      (node (ref "uSD1") (pin "12") (pinfunction "GND_12") (pintype "passive"))
      (node (ref "uSD1") (pin "6") (pinfunction "VSS2_6") (pintype "passive"))
      (node (ref "uSD1") (pin "9") (pintype "passive"))
    )
    (net (code "75") (name "Net-(C14-Pad1)") (class "Default")
      (node (ref "C14") (pin "1") (pinfunction "1_1") (pintype "passive"))
      (node (ref "R6") (pin "1") (pinfunction "1_1") (pintype "passive"))
      (node (ref "Z2") (pin "1") (pinfunction "1_1") (pintype "passive"))
    )
    (net (code "76") (name "Net-(C15-Pad1)") (class "Default")
      (node (ref "C15") (pin "1") (pinfunction "1_1") (pintype "passive"))
      (node (ref "C16") (pin "1") (pinfunction "1_1") (pintype "passive"))
      (node (ref "U1") (pin "E7") (pinfunction "VCAP_E7") (pintype "power_in"))
      (node (ref "U1") (pin "F8") (pinfunction "VCAP_F8") (pintype "power_in"))
    )
    (net (code "77") (name "Net-(U1-BOOT0_{slash}_VPP)") (class "Default")
      (node (ref "J3") (pin "1") (pinfunction "1_1") (pintype "passive"))
      (node (ref "R1") (pin "2") (pinfunction "2_2") (pintype "passive"))
      (node (ref "U1") (pin "D5") (pinfunction "BOOT0_/_VPP_D5") (pintype "input"))
    )
    (net (code "78") (name "Net-(U1-PC14_{slash}_OSC32_IN_{slash}_OSC32_IN)") (class "Default")
      (node (ref "C11") (pin "1") (pinfunction "1_1") (pintype "passive"))
      (node (ref "U1") (pin "A1") (pinfunction "PC14_/_OSC32_IN_/_OSC32_IN_A1") (pintype "bidirectional"))
      (node (ref "Z1") (pin "2") (pinfunction "2_2") (pintype "passive"))
    )
    (net (code "79") (name "Net-(U1-PC15_{slash}_OSC32_OUT_{slash}_OSC32_OUT)") (class "Default")
      (node (ref "C12") (pin "1") (pinfunction "1_1") (pintype "passive"))
      (node (ref "U1") (pin "B1") (pinfunction "PC15_/_OSC32_OUT_/_OSC32_OUT_B1") (pintype "bidirectional"))
      (node (ref "Z1") (pin "1") (pinfunction "1_1") (pintype "passive"))
    )
    (net (code "80") (name "Net-(U1-PDR_ON)") (class "Default")
      (node (ref "R7") (pin "2") (pinfunction "2_2") (pintype "passive"))
      (node (ref "U1") (pin "F7") (pinfunction "PDR_ON_F7") (pintype "input"))
    )
    (net (code "81") (name "VREF_1.65V") (class "Default")
      (node (ref "U1") (pin "E2") (pinfunction "PC2_C_/_ADC3_INN1/ADC3_INP0_/_CDSLEEP_/_DFSDM1_CKIN1_/_SPI2_MISO/I2S2_SDI_/_DFSDM1_CKOUT_/_OTG_HS_ULPI_DIR_/_ETH_MII_TXD2_/_FMC_SDNE0_/_ADC3_INN1_/_ADC3_INP0_E2") (pintype "bidirectional"))
    )
    (net (code "82") (name "unconnected-(U1-PA0_{slash}_ADC1_INP16{slash}WKUP0_{slash}_TIM2_CH1{slash}TIM2_ETR_{slash}_TIM5_CH1_{slash}_TIM8_ETR_{slash}_TIM15_BKIN_{slash}_USART2_CTS{slash}USART2_NSS_{slash}_UART4_TX_{slash}_SDMMC2_CMD_{slash}_SAI2_SD_B_{slash}_ETH_MII_CRS_{slash}_ADC1_INP16_{slash}_WKUP0-PadG2)") (class "Default")
      (node (ref "U1") (pin "G2") (pinfunction "PA0_/_ADC1_INP16/WKUP0_/_TIM2_CH1/TIM2_ETR_/_TIM5_CH1_/_TIM8_ETR_/_TIM15_BKIN_/_USART2_CTS/USART2_NSS_/_UART4_TX_/_SDMMC2_CMD_/_SAI2_SD_B_/_ETH_MII_CRS_/_ADC1_INP16_/_WKUP0_G2") (pintype "bidirectional"))
    )
    (net (code "83") (name "unconnected-(U1-PA1_{slash}_ADC1_INN16{slash}ADC1_INP17_{slash}_TIM2_CH2_{slash}_TIM5_CH2_{slash}_LPTIM3_OUT_{slash}_TIM15_CH1N_{slash}_USART2_RTS{slash}USART2_DE_{slash}_UART4_RX_{slash}_QUADSPI_BK1_IO3_{slash}_SAI2_MCLK_B_{slash}_ETH_MII_RX_CLK{slash}ETH_RMII_REF_CLK_{slash}_LCD_R2_{slash}_ADC1_INN16_{slash}_ADC1_INP17-PadH2)") (class "Default")
      (node (ref "U1") (pin "H2") (pinfunction "PA1_/_ADC1_INN16/ADC1_INP17_/_TIM2_CH2_/_TIM5_CH2_/_LPTIM3_OUT_/_TIM15_CH1N_/_USART2_RTS/USART2_DE_/_UART4_RX_/_QUADSPI_BK1_IO3_/_SAI2_MCLK_B_/_ETH_MII_RX_CLK/ETH_RMII_REF_CLK_/_LCD_R2_/_ADC1_INN16_/_ADC1_INP17_H2") (pintype "bidirectional"))
    )
    (net (code "84") (name "unconnected-(U1-PB2_{slash}_COMP1_INP_{slash}_RTC_OUT_{slash}_SAI1_D1_{slash}_DFSDM1_CKIN1_{slash}_SAI1_SD_A_{slash}_SPI3_MOSI{slash}I2S3_SDO_{slash}_SAI4_SD_A_{slash}_QUADSPI_CLK_{slash}_SAI4_D1_{slash}_COMP1_INP-PadG5)") (class "Default")
      (node (ref "U1") (pin "G5") (pinfunction "PB2_/_COMP1_INP_/_RTC_OUT_/_SAI1_D1_/_DFSDM1_CKIN1_/_SAI1_SD_A_/_SPI3_MOSI/I2S3_SDO_/_SAI4_SD_A_/_QUADSPI_CLK_/_SAI4_D1_/_COMP1_INP_G5") (pintype "bidirectional"))
    )
    (net (code "85") (name "unconnected-(U1-PD0_{slash}_DFSDM1_CKIN6_{slash}_SAI3_SCK_A_{slash}_UART4_RX_{slash}_FDCAN1_RX_{slash}_FMC_D2{slash}FMC_DA2-PadD8)") (class "Default")
      (node (ref "U1") (pin "D8") (pinfunction "PD0_/_DFSDM1_CKIN6_/_SAI3_SCK_A_/_UART4_RX_/_FDCAN1_RX_/_FMC_D2/FMC_DA2_D8") (pintype "bidirectional"))
    )
    (net (code "86") (name "unconnected-(U1-PD4_{slash}_HRTIM_FLT3_{slash}_SAI3_FS_A_{slash}_USART2_RTS{slash}USART2_DE_{slash}_FDCAN1_RXFD_MODE_{slash}_FMC_NOE-PadD7)") (class "Default")
      (node (ref "U1") (pin "D7") (pinfunction "PD4_/_HRTIM_FLT3_/_SAI3_FS_A_/_USART2_RTS/USART2_DE_/_FDCAN1_RXFD_MODE_/_FMC_NOE_D7") (pintype "bidirectional"))
    )
    (net (code "87") (name "unconnected-(U1-PD7_{slash}_DFSDM1_DATIN4_{slash}_SPI1_MOSI{slash}I2S1_SDO_{slash}_DFSDM1_CKIN1_{slash}_USART2_CK_{slash}_SPDIFRX1_IN1_{slash}_SDMMC2_CMD_{slash}_FMC_NE1-PadD6)") (class "Default")
      (node (ref "U1") (pin "D6") (pinfunction "PD7_/_DFSDM1_DATIN4_/_SPI1_MOSI/I2S1_SDO_/_DFSDM1_CKIN1_/_USART2_CK_/_SPDIFRX1_IN1_/_SDMMC2_CMD_/_FMC_NE1_D6") (pintype "bidirectional"))
    )
    (net (code "88") (name "unconnected-(U1-PD14_{slash}_TIM4_CH3_{slash}_SAI3_MCLK_B_{slash}_UART8_CTS_{slash}_FMC_D0{slash}FMC_DA0-PadH8)") (class "Default")
      (node (ref "U1") (pin "H8") (pinfunction "PD14_/_TIM4_CH3_/_SAI3_MCLK_B_/_UART8_CTS_/_FMC_D0/FMC_DA0_H8") (pintype "bidirectional"))
    )
    (net (code "89") (name "unconnected-(U1-PE5_{slash}_TRACED2_{slash}_SAI1_CK2_{slash}_DFSDM1_CKIN3_{slash}_TIM15_CH1_{slash}_SPI4_MISO_{slash}_SAI1_SCK_A_{slash}_SAI4_SCK_A_{slash}_SAI4_CK2_{slash}_FMC_A21_{slash}_DCMI_D6_{slash}_LCD_G0-PadD3)") (class "Default")
      (node (ref "U1") (pin "D3") (pinfunction "PE5_/_TRACED2_/_SAI1_CK2_/_DFSDM1_CKIN3_/_TIM15_CH1_/_SPI4_MISO_/_SAI1_SCK_A_/_SAI4_SCK_A_/_SAI4_CK2_/_FMC_A21_/_DCMI_D6_/_LCD_G0_D3") (pintype "bidirectional"))
    )
    (net (code "90") (name "unconnected-(U1-PE10_{slash}_COMP2_INM_{slash}_TIM1_CH2N_{slash}_DFSDM1_DATIN4_{slash}_UART7_CTS_{slash}_QUADSPI_BK2_IO3_{slash}_FMC_D7{slash}FMC_DA7_{slash}_COMP2_INM-PadG6)") (class "Default")
      (node (ref "U1") (pin "G6") (pinfunction "PE10_/_COMP2_INM_/_TIM1_CH2N_/_DFSDM1_DATIN4_/_UART7_CTS_/_QUADSPI_BK2_IO3_/_FMC_D7/FMC_DA7_/_COMP2_INM_G6") (pintype "bidirectional"))
    )
    (net (code "91") (name "unconnected-(U1-PE14_{slash}_TIM1_CH4_{slash}_SPI4_MOSI_{slash}_SAI2_MCLK_B_{slash}_FMC_D11{slash}FMC_DA11_{slash}_LCD_CLK-PadG7)") (class "Default")
      (node (ref "U1") (pin "G7") (pinfunction "PE14_/_TIM1_CH4_/_SPI4_MOSI_/_SAI2_MCLK_B_/_FMC_D11/FMC_DA11_/_LCD_CLK_G7") (pintype "bidirectional"))
    )
    (net (code "92") (name "unconnected-(U1-PE15_{slash}_TIM1_BKIN_{slash}_FMC_D12{slash}FMC_DA12_{slash}_TIM1_BKIN_COMP12{slash}COMP_TIM1_BKIN_{slash}_LCD_R7-PadH7)") (class "Default")
      (node (ref "U1") (pin "H7") (pinfunction "PE15_/_TIM1_BKIN_/_FMC_D12/FMC_DA12_/_TIM1_BKIN_COMP12/COMP_TIM1_BKIN_/_LCD_R7_H7") (pintype "bidirectional"))
    )
  )
)
